# power.net
KiCad netlist of a schematic drawn in Altium Designer
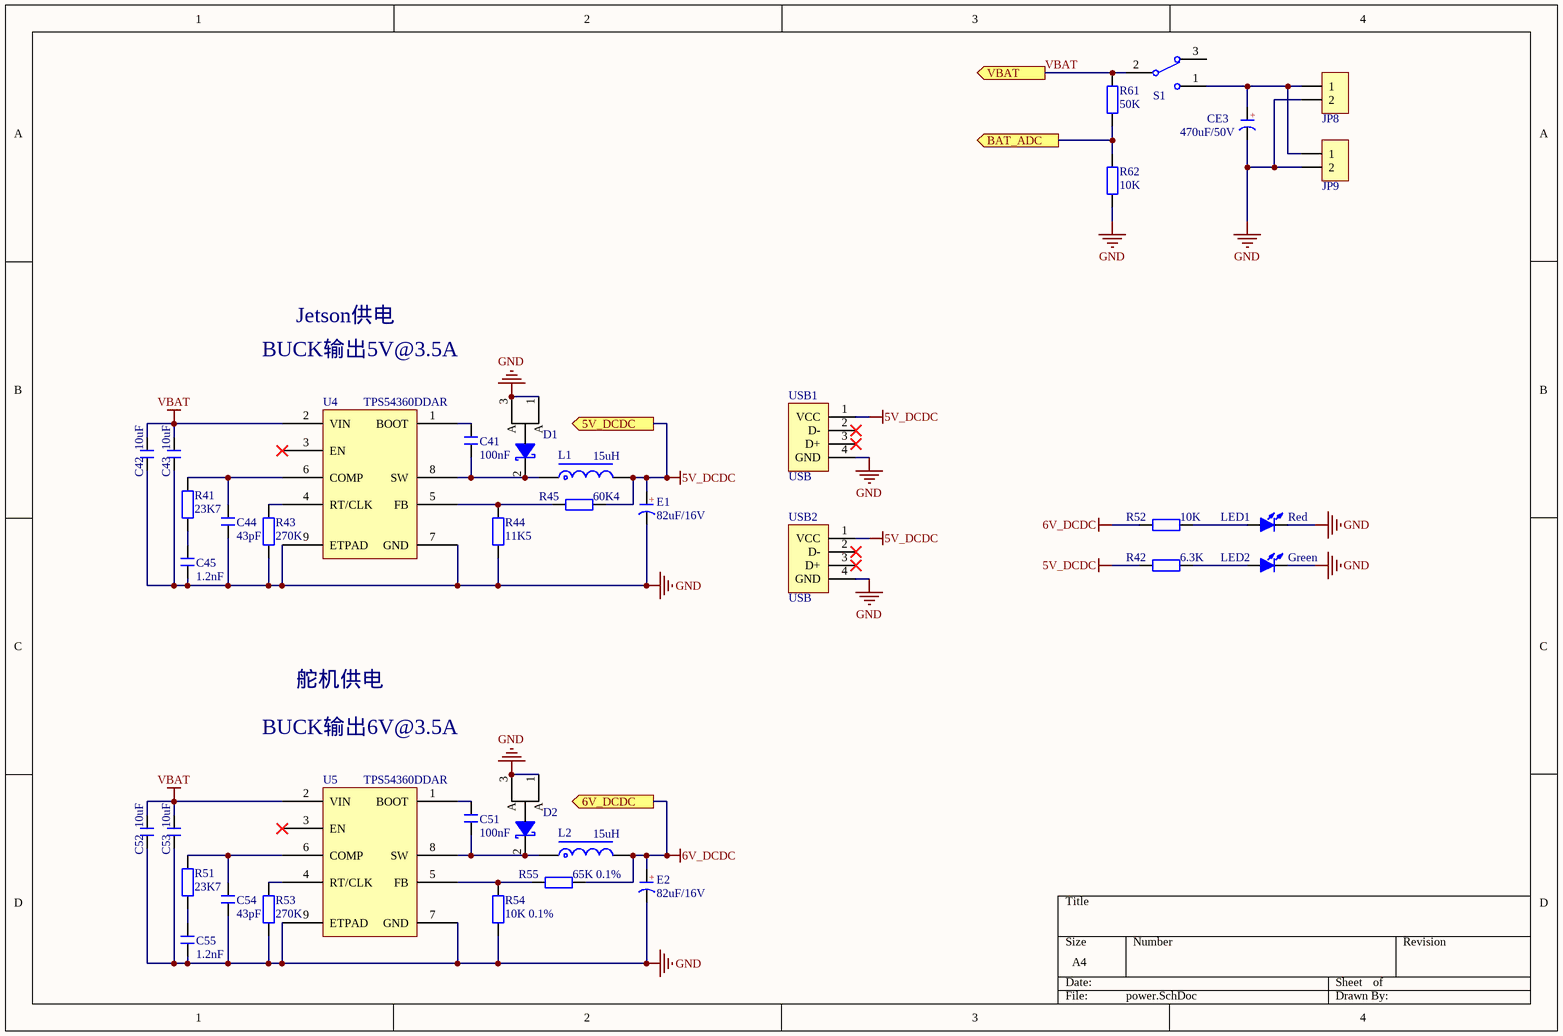
[diagram p0: power.SchDoc]

(export (version "E")
  (design (tool "Eeschema 10.0.6"))
  (components
    (comp (ref "C41") (value "100nF") (footprint "C 0402_M") (libsource (lib "RLC") (part "C_100nF_0402")))
    (comp (ref "C42") (value "10uF") (footprint "C 2220_M") (libsource (lib "RLC") (part "C_10uF_100V_2220")))
    (comp (ref "C43") (value "10uF") (footprint "C 2220_M") (libsource (lib "RLC") (part "C_10uF_100V_2220")))
    (comp (ref "C44") (value "43pF") (footprint "C 0402_M") (libsource (lib "RLC") (part "C_43pF_0402")))
    (comp (ref "C45") (value "1.2nF") (footprint "C 0402_M") (libsource (lib "RLC") (part "C_1.2nF_0402")))
    (comp (ref "C51") (value "100nF") (footprint "C 0402_M") (libsource (lib "RLC") (part "C_100nF_0402")))
    (comp (ref "C52") (value "10uF") (footprint "C 2220_M") (libsource (lib "RLC") (part "C_10uF_100V_2220")))
    (comp (ref "C53") (value "10uF") (footprint "C 2220_M") (libsource (lib "RLC") (part "C_10uF_100V_2220")))
    (comp (ref "C54") (value "43pF") (footprint "C 0402_M") (libsource (lib "RLC") (part "C_43pF_0402")))
    (comp (ref "C55") (value "1.2nF") (footprint "C 0402_M") (libsource (lib "RLC") (part "C_1.2nF_0402")))
    (comp (ref "CE3")
      (value "470uF/50V")
      (footprint "CAP 5.0*10*16")
      (description "直插电解电容")
      (libsource (lib "RLC") (part "CE"))
    )
    (comp (ref "D1")
      (value "50WQ10FNPBF")
      (footprint "D-PAK")
      (description "Vishay-Semiconductor 50WQ10FNPBF Type: Schottky  VRRM: 100 V  Io: 5.5 A")
      (fields (field (name "PUBLISHER") "Altium Limited"))
      (libsource (lib "transistors") (part "Diode Schottky_100V_5.5A"))
    )
    (comp (ref "D2")
      (value "50WQ10FNPBF")
      (footprint "D-PAK")
      (description "Vishay-Semiconductor 50WQ10FNPBF Type: Schottky  VRRM: 100 V  Io: 5.5 A")
      (fields (field (name "PUBLISHER") "Altium Limited"))
      (libsource (lib "transistors") (part "Diode Schottky_100V_5.5A"))
    )
    (comp (ref "E1")
      (value "82uF/16V")
      (footprint "CM C(5*5.4)")
      (description "Panasonic 16SVPF82M Cap: 82 µF  Total Derated Cap: 82 µF  VDC: 16 V  ESR: 27 mΩ  Package: 5x5.9")
      (libsource (lib "RLC") (part "CE_SMD_82uF_16V"))
    )
    (comp (ref "E2")
      (value "82uF/16V")
      (footprint "CM C(5*5.4)")
      (description "Panasonic 16SVPF82M Cap: 82 µF  Total Derated Cap: 82 µF  VDC: 16 V  ESR: 27 mΩ  Package: 5x5.9")
      (libsource (lib "RLC") (part "CE_SMD_82uF_16V"))
    )
    (comp (ref "JP8")
      (value "HDR-1X2")
      (footprint "TX60-LI-S")
      (description "2P接插件")
      (libsource (lib "connectors") (part "Header 2"))
    )
    (comp (ref "JP9")
      (value "HDR-1X2")
      (footprint "TX60-LI-S")
      (description "2P接插件")
      (libsource (lib "connectors") (part "Header 2"))
    )
    (comp (ref "L1")
      (value "15uH")
      (footprint "CDRH127")
      (description "功率屏蔽电感Sumida CDRH127/LDNP-150MC L: 15 µH  DCR: 26.4 mΩ  IDC: 5.65 A")
      (fields (field (name "版权归属") "封装库来自淘宝 ID：黄晶宝石"))
      (libsource (lib "RLC") (part "L-CDRH_15uH_5.65A"))
    )
    (comp (ref "L2")
      (value "15uH")
      (footprint "CDRH127")
      (description "功率屏蔽电感Sumida CDRH127/LDNP-150MC L: 15 µH  DCR: 26.4 mΩ  IDC: 5.65 A")
      (fields (field (name "版权归属") "封装库来自淘宝 ID：黄晶宝石"))
      (libsource (lib "RLC") (part "L-CDRH_15uH_5.65A"))
    )
    (comp (ref "LED1")
      (value "Red")
      (footprint "LED 1206R")
      (description "贴片LED")
      (fields (field (name "版权归属") "封装库来自淘宝 ID：黄晶宝石"))
      (libsource (lib "transistors") (part "LED-SMD"))
    )
    (comp (ref "LED2")
      (value "Green")
      (footprint "LED 1206G")
      (description "贴片LED")
      (fields (field (name "版权归属") "封装库来自淘宝 ID：黄晶宝石"))
      (libsource (lib "transistors") (part "LED-SMD"))
    )
    (comp (ref "R41")
      (value "23K7")
      (footprint "R 0402_M")
      (description "Yageo AC0402FR-0723K7L Resistance: 23.7 kΩ  Tolerance: 1.0%  Power: 63 mW")
      (libsource (lib "RLC") (part "R_23K7_0402_1%"))
    )
    (comp (ref "R42")
      (value "6.3K")
      (footprint "R 0603_M")
      (description "贴片电阻")
      (libsource (lib "RLC") (part "R_10K_0603"))
    )
    (comp (ref "R43")
      (value "270K")
      (footprint "R 0603_M")
      (description "Yageo RC0603FR-07270KL Resistance: 270 kΩ  Tolerance: 1.0%  Power: 100 mW")
      (libsource (lib "RLC") (part "R_270K_0603_1%"))
    )
    (comp (ref "R44")
      (value "11K5")
      (footprint "R 0603_M")
      (description "Yageo RC0603FR-0711K5L Resistance: 11.5 kΩ  Tolerance: 1.0%  Power: 100 mW")
      (libsource (lib "RLC") (part "R_11K5_0603_1%"))
    )
    (comp (ref "R45")
      (value "60K4")
      (footprint "R 0402_M")
      (description "Vishay-Dale CRCW040260K4FKED Resistance: 60.4 kΩ Tolerance: 1.0%  Power: 63 mW")
      (libsource (lib "RLC") (part "R_60K4_0402_1%"))
    )
    (comp (ref "R51")
      (value "23K7")
      (footprint "R 0402_M")
      (description "Yageo AC0402FR-0723K7L Resistance: 23.7 kΩ  Tolerance: 1.0%  Power: 63 mW")
      (libsource (lib "RLC") (part "R_23K7_0402_1%"))
    )
    (comp (ref "R52")
      (value "10K")
      (footprint "R 0402_M")
      (description "贴片电阻")
      (libsource (lib "RLC") (part "R_10K_0603"))
    )
    (comp (ref "R53")
      (value "270K")
      (footprint "R 0603_M")
      (description "Yageo RC0603FR-07270KL Resistance: 270 kΩ  Tolerance: 1.0%  Power: 100 mW")
      (libsource (lib "RLC") (part "R_270K_0603_1%"))
    )
    (comp (ref "R54")
      (value "10K 0.1%")
      (footprint "R 0603_M")
      (description "贴片电阻")
      (libsource (lib "RLC") (part "R"))
    )
    (comp (ref "R55")
      (value "65K 0.1%")
      (footprint "R 0402_M")
      (description "贴片电阻")
      (libsource (lib "RLC") (part "R"))
    )
    (comp (ref "R61")
      (value "50K")
      (footprint "R 0402_M")
      (description "贴片电阻")
      (libsource (lib "RLC") (part "R_10K_0603"))
    )
    (comp (ref "R62")
      (value "10K")
      (footprint "R 0402_M")
      (description "贴片电阻")
      (libsource (lib "RLC") (part "R_10K_0603"))
    )
    (comp (ref "S1")
      (value "SW-SPDT")
      (footprint "SS12D10")
      (description "单刀双掷开关 3脚船型、钮子、拨动开关 SPDT Subminiature Toggle Switch")
      (fields (field (name "PUBLISHER") "Altium Limited"))
      (libsource (lib "connectors") (part "SW-SPDT"))
    )
    (comp (ref "U4")
      (value "TPS54360DDAR")
      (footprint "SOP127P600X170_HS-9N")
      (libsource (lib "IC") (part "TPS54360DDAR"))
    )
    (comp (ref "U5")
      (value "TPS54360DDAR")
      (footprint "SOP127P600X170_HS-9N")
      (libsource (lib "IC") (part "TPS54360DDAR"))
    )
    (comp (ref "USB1")
      (value "USB")
      (footprint "USB-A/S_B")
      (description "USB-A型母接口")
      (libsource (lib "usb") (part "USB-A/S"))
    )
    (comp (ref "USB2")
      (value "USB")
      (footprint "USB-A/S_B")
      (description "USB-A型母接口")
      (libsource (lib "usb") (part "USB-A/S"))
    )
  )
  (nets
    (net (code "1") (name "/BAT_ADC") (class "Default")
      (node (ref "R61") (pin "1") (pinfunction "1_1") (pintype "passive"))
      (node (ref "R62") (pin "2") (pinfunction "2_2") (pintype "passive"))
    )
    (net (code "2") (name "5V_DCDC") (class "Default")
      (node (ref "E1") (pin "1") (pinfunction "A_1") (pintype "passive"))
      (node (ref "L1") (pin "2") (pinfunction "2_2") (pintype "passive"))
      (node (ref "R42") (pin "1") (pinfunction "1_1") (pintype "passive"))
      (node (ref "R45") (pin "2") (pinfunction "2_2") (pintype "passive"))
      (node (ref "USB1") (pin "1") (pinfunction "VCC_1") (pintype "passive"))
      (node (ref "USB2") (pin "1") (pinfunction "VCC_1") (pintype "passive"))
    )
    (net (code "3") (name "6V_DCDC") (class "Default")
      (node (ref "E2") (pin "1") (pinfunction "A_1") (pintype "passive"))
      (node (ref "L2") (pin "2") (pinfunction "2_2") (pintype "passive"))
      (node (ref "R52") (pin "1") (pinfunction "1_1") (pintype "passive"))
      (node (ref "R55") (pin "2") (pinfunction "2_2") (pintype "passive"))
    )
    (net (code "4") (name "GND") (class "Default")
      (node (ref "C42") (pin "1") (pinfunction "1_1") (pintype "passive"))
      (node (ref "C43") (pin "1") (pinfunction "1_1") (pintype "passive"))
      (node (ref "C44") (pin "1") (pinfunction "1_1") (pintype "passive"))
      (node (ref "C45") (pin "1") (pinfunction "1_1") (pintype "passive"))
      (node (ref "C52") (pin "1") (pinfunction "1_1") (pintype "passive"))
      (node (ref "C53") (pin "1") (pinfunction "1_1") (pintype "passive"))
      (node (ref "C54") (pin "1") (pinfunction "1_1") (pintype "passive"))
      (node (ref "C55") (pin "1") (pinfunction "1_1") (pintype "passive"))
      (node (ref "CE3") (pin "2") (pinfunction "K_2") (pintype "passive"))
      (node (ref "D1") (pin "1") (pinfunction "A_1") (pintype "passive"))
      (node (ref "D1") (pin "3") (pinfunction "A_3") (pintype "passive"))
      (node (ref "D2") (pin "1") (pinfunction "A_1") (pintype "passive"))
      (node (ref "D2") (pin "3") (pinfunction "A_3") (pintype "passive"))
      (node (ref "E1") (pin "2") (pinfunction "K_2") (pintype "passive"))
      (node (ref "E2") (pin "2") (pinfunction "K_2") (pintype "passive"))
      (node (ref "JP8") (pin "2") (pinfunction "2_2") (pintype "passive"))
      (node (ref "JP9") (pin "2") (pinfunction "2_2") (pintype "passive"))
      (node (ref "LED1") (pin "2") (pinfunction "K_2") (pintype "passive"))
      (node (ref "LED2") (pin "2") (pinfunction "K_2") (pintype "passive"))
      (node (ref "R43") (pin "1") (pinfunction "1_1") (pintype "passive"))
      (node (ref "R44") (pin "2") (pinfunction "2_2") (pintype "passive"))
      (node (ref "R53") (pin "1") (pinfunction "1_1") (pintype "passive"))
      (node (ref "R54") (pin "2") (pinfunction "2_2") (pintype "passive"))
      (node (ref "R62") (pin "1") (pinfunction "1_1") (pintype "passive"))
      (node (ref "U4") (pin "7") (pinfunction "GND_7") (pintype "passive"))
      (node (ref "U4") (pin "9") (pinfunction "ETPAD_9") (pintype "passive"))
      (node (ref "U5") (pin "7") (pinfunction "GND_7") (pintype "passive"))
      (node (ref "U5") (pin "9") (pinfunction "ETPAD_9") (pintype "passive"))
      (node (ref "USB1") (pin "4") (pinfunction "GND_4") (pintype "passive"))
      (node (ref "USB2") (pin "4") (pinfunction "GND_4") (pintype "passive"))
    )
    (net (code "5") (name "Net-(C45-Pad2)") (class "Default")
      (node (ref "C45") (pin "2") (pinfunction "2_2") (pintype "passive"))
      (node (ref "R41") (pin "1") (pinfunction "1_1") (pintype "passive"))
    )
    (net (code "6") (name "Net-(C55-Pad2)") (class "Default")
      (node (ref "C55") (pin "2") (pinfunction "2_2") (pintype "passive"))
      (node (ref "R51") (pin "1") (pinfunction "1_1") (pintype "passive"))
    )
    (net (code "7") (name "Net-(CE3-A)") (class "Default")
      (node (ref "CE3") (pin "1") (pinfunction "A_1") (pintype "passive"))
      (node (ref "JP8") (pin "1") (pinfunction "1_1") (pintype "passive"))
      (node (ref "JP9") (pin "1") (pinfunction "1_1") (pintype "passive"))
      (node (ref "S1") (pin "1") (pintype "passive"))
    )
    (net (code "8") (name "Net-(D1-K)") (class "Default")
      (node (ref "C41") (pin "1") (pinfunction "1_1") (pintype "passive"))
      (node (ref "D1") (pin "2") (pinfunction "K_2") (pintype "passive"))
      (node (ref "L1") (pin "1") (pinfunction "1_1") (pintype "passive"))
      (node (ref "U4") (pin "8") (pinfunction "SW_8") (pintype "passive"))
    )
    (net (code "9") (name "Net-(D2-K)") (class "Default")
      (node (ref "C51") (pin "1") (pinfunction "1_1") (pintype "passive"))
      (node (ref "D2") (pin "2") (pinfunction "K_2") (pintype "passive"))
      (node (ref "L2") (pin "1") (pinfunction "1_1") (pintype "passive"))
      (node (ref "U5") (pin "8") (pinfunction "SW_8") (pintype "passive"))
    )
    (net (code "10") (name "Net-(LED1-A)") (class "Default")
      (node (ref "LED1") (pin "1") (pinfunction "A_1") (pintype "passive"))
      (node (ref "R52") (pin "2") (pinfunction "2_2") (pintype "passive"))
    )
    (net (code "11") (name "Net-(LED2-A)") (class "Default")
      (node (ref "LED2") (pin "1") (pinfunction "A_1") (pintype "passive"))
      (node (ref "R42") (pin "2") (pinfunction "2_2") (pintype "passive"))
    )
    (net (code "12") (name "Net-(U4-BOOT)") (class "Default")
      (node (ref "C41") (pin "2") (pinfunction "2_2") (pintype "passive"))
      (node (ref "U4") (pin "1") (pinfunction "BOOT_1") (pintype "passive"))
    )
    (net (code "13") (name "Net-(U4-COMP)") (class "Default")
      (node (ref "C44") (pin "2") (pinfunction "2_2") (pintype "passive"))
      (node (ref "R41") (pin "2") (pinfunction "2_2") (pintype "passive"))
      (node (ref "U4") (pin "6") (pinfunction "COMP_6") (pintype "passive"))
    )
    (net (code "14") (name "Net-(U4-FB)") (class "Default")
      (node (ref "R44") (pin "1") (pinfunction "1_1") (pintype "passive"))
      (node (ref "R45") (pin "1") (pinfunction "1_1") (pintype "passive"))
      (node (ref "U4") (pin "5") (pinfunction "FB_5") (pintype "passive"))
    )
    (net (code "15") (name "Net-(U4-RT{slash}CLK)") (class "Default")
      (node (ref "R43") (pin "2") (pinfunction "2_2") (pintype "passive"))
      (node (ref "U4") (pin "4") (pinfunction "RT/CLK_4") (pintype "passive"))
    )
    (net (code "16") (name "Net-(U5-BOOT)") (class "Default")
      (node (ref "C51") (pin "2") (pinfunction "2_2") (pintype "passive"))
      (node (ref "U5") (pin "1") (pinfunction "BOOT_1") (pintype "passive"))
    )
    (net (code "17") (name "Net-(U5-COMP)") (class "Default")
      (node (ref "C54") (pin "2") (pinfunction "2_2") (pintype "passive"))
      (node (ref "R51") (pin "2") (pinfunction "2_2") (pintype "passive"))
      (node (ref "U5") (pin "6") (pinfunction "COMP_6") (pintype "passive"))
    )
    (net (code "18") (name "Net-(U5-FB)") (class "Default")
      (node (ref "R54") (pin "1") (pinfunction "1_1") (pintype "passive"))
      (node (ref "R55") (pin "1") (pinfunction "1_1") (pintype "passive"))
      (node (ref "U5") (pin "5") (pinfunction "FB_5") (pintype "passive"))
    )
    (net (code "19") (name "Net-(U5-RT{slash}CLK)") (class "Default")
      (node (ref "R53") (pin "2") (pinfunction "2_2") (pintype "passive"))
      (node (ref "U5") (pin "4") (pinfunction "RT/CLK_4") (pintype "passive"))
    )
    (net (code "20") (name "VBAT") (class "Default")
      (node (ref "C42") (pin "2") (pinfunction "2_2") (pintype "passive"))
      (node (ref "C43") (pin "2") (pinfunction "2_2") (pintype "passive"))
      (node (ref "C52") (pin "2") (pinfunction "2_2") (pintype "passive"))
      (node (ref "C53") (pin "2") (pinfunction "2_2") (pintype "passive"))
      (node (ref "R61") (pin "2") (pinfunction "2_2") (pintype "passive"))
      (node (ref "S1") (pin "2") (pintype "passive"))
      (node (ref "U4") (pin "2") (pinfunction "VIN_2") (pintype "passive"))
      (node (ref "U5") (pin "2") (pinfunction "VIN_2") (pintype "passive"))
    )
    (net (code "21") (name "unconnected-(S1-Pad3)") (class "Default")
      (node (ref "S1") (pin "3") (pintype "passive"))
    )
    (net (code "22") (name "unconnected-(U4-EN-Pad3)") (class "Default")
      (node (ref "U4") (pin "3") (pinfunction "EN_3") (pintype "passive+no_connect"))
    )
    (net (code "23") (name "unconnected-(U5-EN-Pad3)") (class "Default")
      (node (ref "U5") (pin "3") (pinfunction "EN_3") (pintype "passive+no_connect"))
    )
    (net (code "24") (name "unconnected-(USB1-D+-Pad3)") (class "Default")
      (node (ref "USB1") (pin "3") (pinfunction "D+_3") (pintype "passive+no_connect"))
    )
    (net (code "25") (name "unconnected-(USB1-D--Pad2)") (class "Default")
      (node (ref "USB1") (pin "2") (pinfunction "D-_2") (pintype "passive+no_connect"))
    )
    (net (code "26") (name "unconnected-(USB2-D+-Pad3)") (class "Default")
      (node (ref "USB2") (pin "3") (pinfunction "D+_3") (pintype "passive+no_connect"))
    )
    (net (code "27") (name "unconnected-(USB2-D--Pad2)") (class "Default")
      (node (ref "USB2") (pin "2") (pinfunction "D-_2") (pintype "passive+no_connect"))
    )
  )
)
